# TMP235AQDB2TQ1.net
KiCad netlist of a schematic drawn in Altium Designer
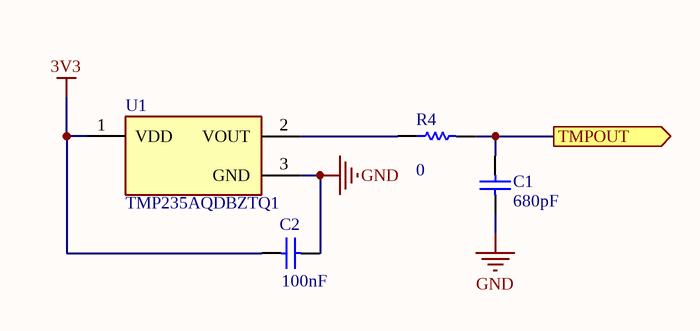
[diagram p0: TMP235AQDB2TQ1.SchDoc]

(export (version "E")
  (design (tool "Eeschema 10.0.6"))
  (components
    (comp (ref "C1")
      (value "680pF")
      (footprint "1608[0603]")
      (description "Capacitor")
      (fields (field (name "Comment") "Cap") (field (name "PUBLISHER") "Altium Limited"))
      (libsource (lib "Miscellaneous Devices") (part "Cap"))
    )
    (comp (ref "C2")
      (value "100nF")
      (footprint "1608[0603]")
      (description "Capacitor")
      (fields (field (name "Comment") "Cap") (field (name "PUBLISHER") "Altium Limited"))
      (libsource (lib "Miscellaneous Devices") (part "Cap"))
    )
    (comp (ref "R4")
      (value "0")
      (footprint "0402-A")
      (description "Resistor")
      (fields (field (name "Comment") "Res1") (field (name "PUBLISHER") "Altium Limited"))
      (libsource (lib "Miscellaneous Devices") (part "Res1"))
    )
    (comp (ref "U1")
      (value "TMP235AQDBZTQ1")
      (footprint "FP-DBZ0003A-MFG")
      (description "LOW-POWER HIGH-ACCURACY ANALOG O")
      (fields
        (field (name "MANUFACTURER") "Texas Instruments")
        (field (name "MANUFACTURER PART NUMBER") "TMP235A2DBZR")
      )
      (libsource (lib "Altium Content Vault") (part "1212246baba8f64ab0dd7b63bd818eb"))
    )
  )
  (nets
    (net (code "1") (name "/TMPOUT") (class "Default")
      (node (ref "C1") (pin "1") (pinfunction "1_1") (pintype "passive"))
      (node (ref "R4") (pin "2") (pinfunction "2_2") (pintype "passive"))
    )
    (net (code "2") (name "3V3") (class "Default")
      (node (ref "C2") (pin "1") (pinfunction "1_1") (pintype "passive"))
      (node (ref "U1") (pin "1") (pinfunction "VDD_1") (pintype "power_in"))
    )
    (net (code "3") (name "GND") (class "Default")
      (node (ref "C1") (pin "2") (pinfunction "2_2") (pintype "passive"))
      (node (ref "C2") (pin "2") (pinfunction "2_2") (pintype "passive"))
      (node (ref "U1") (pin "3") (pinfunction "GND_3") (pintype "power_in"))
    )
    (net (code "4") (name "Net-(U1-VOUT)") (class "Default")
      (node (ref "R4") (pin "1") (pinfunction "1_1") (pintype "passive"))
      (node (ref "U1") (pin "2") (pinfunction "VOUT_2") (pintype "passive"))
    )
  )
)
